# counter.net
KiCad netlist of a schematic drawn in EAGLE
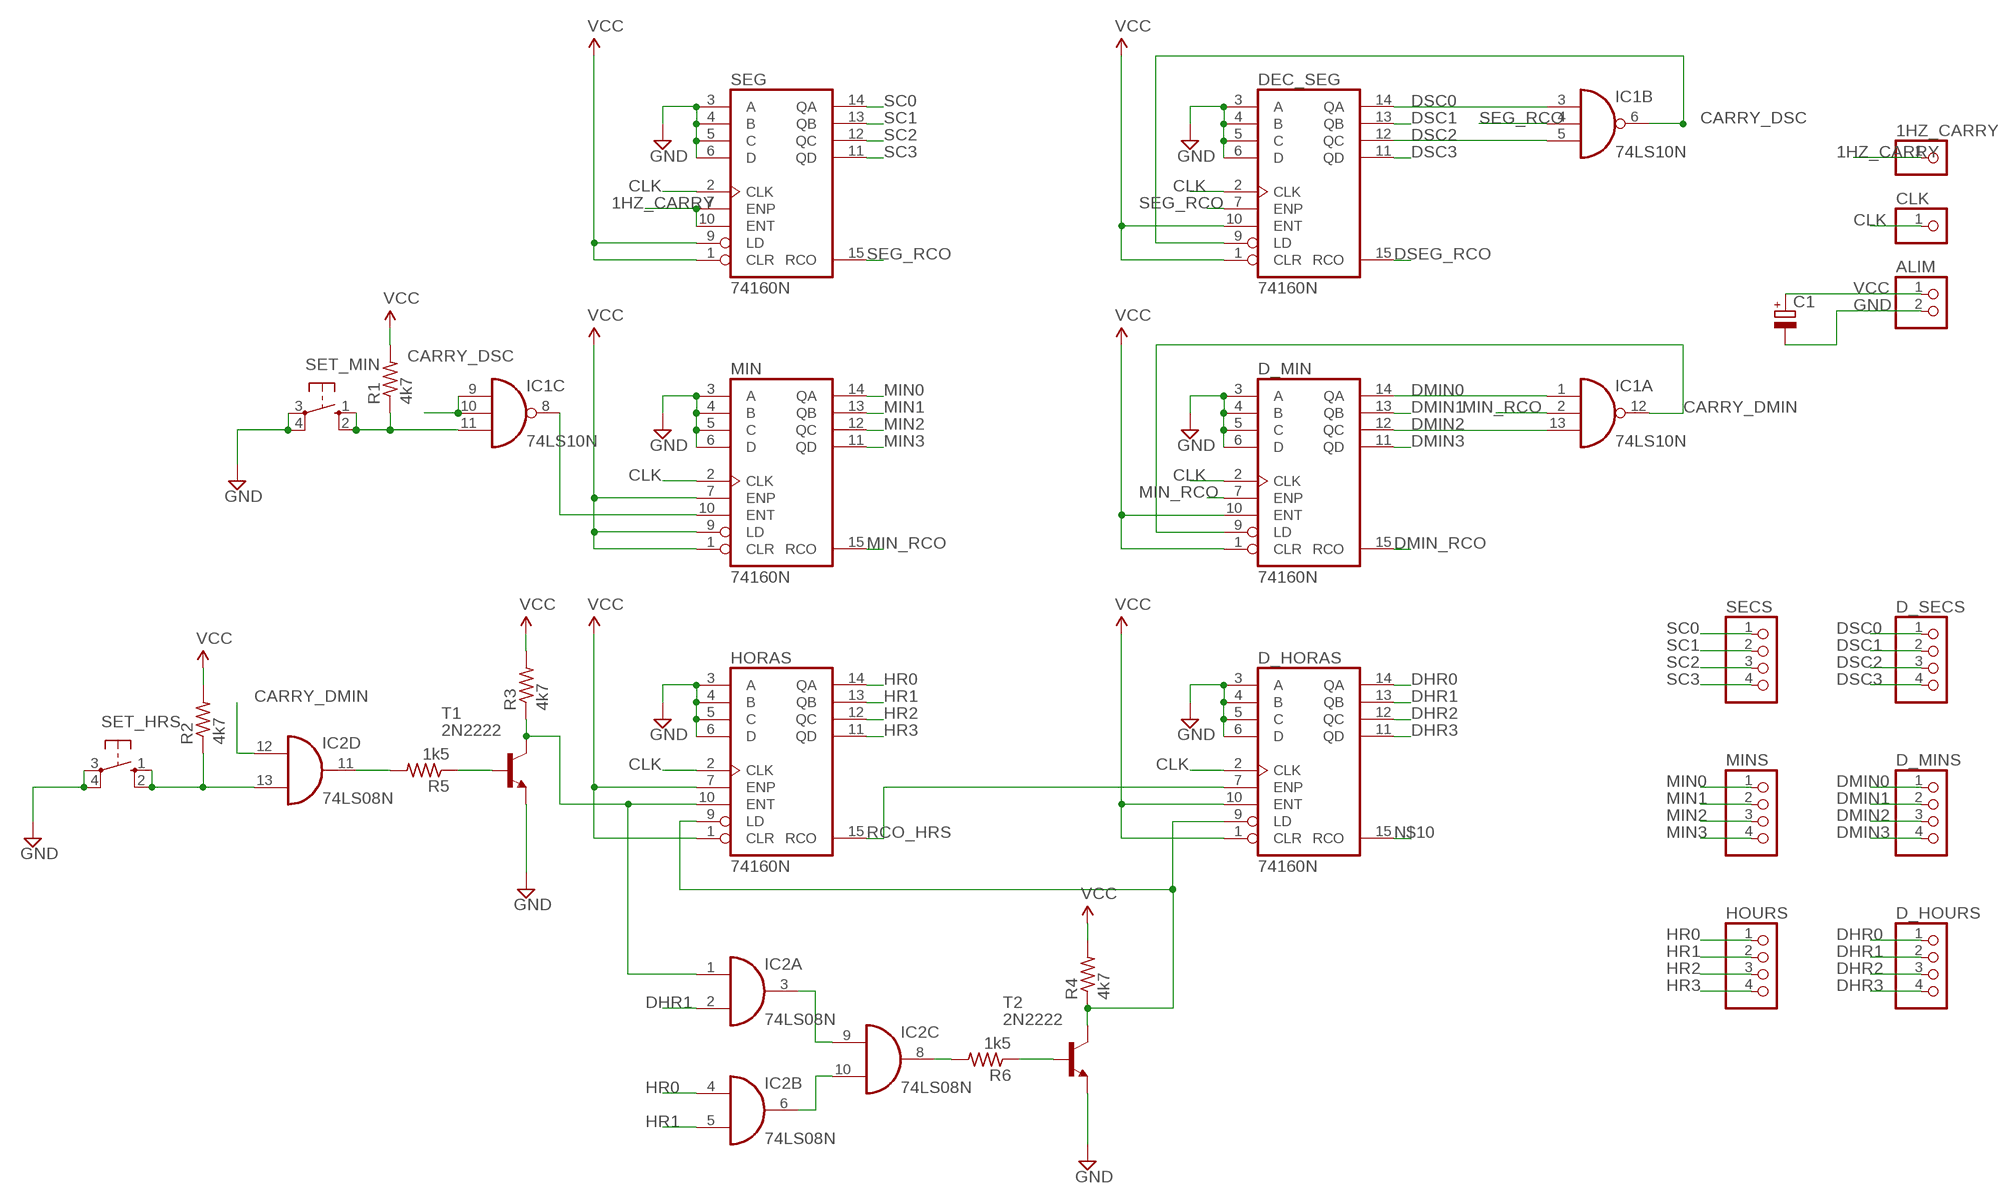
[diagram p0: schematic, sheet 1]

(export (version "E")
  (design (tool "Eeschema 10.0.6"))
  (components
    (comp (ref "1HZ_CARRY")
      (value "PINHD-1X1")
      (footprint "eagle-import:1X01")
      (libsource (lib "eagle-import") (part "PINHD-1X1"))
    )
    (comp (ref "ALIM")
      (value "PINHD-1X2")
      (footprint "eagle-import:1X02")
      (libsource (lib "eagle-import") (part "PINHD-1X2"))
    )
    (comp (ref "C1")
      (value "CPOL-EUE2-5")
      (footprint "eagle-import:E2-5")
      (libsource (lib "eagle-import") (part "CPOL-EUE2-5"))
    )
    (comp (ref "CLK")
      (value "PINHD-1X1")
      (footprint "eagle-import:1X01")
      (libsource (lib "eagle-import") (part "PINHD-1X1"))
    )
    (comp (ref "DEC_SEG")
      (value "74160N")
      (footprint "eagle-import:DIL16")
      (libsource (lib "eagle-import") (part "74160N"))
    )
    (comp (ref "D_HORAS")
      (value "74160N")
      (footprint "eagle-import:DIL16")
      (libsource (lib "eagle-import") (part "74160N"))
    )
    (comp (ref "D_HOURS")
      (value "PINHD-1X4")
      (footprint "eagle-import:1X04")
      (libsource (lib "eagle-import") (part "PINHD-1X4"))
    )
    (comp (ref "D_MIN")
      (value "74160N")
      (footprint "eagle-import:DIL16")
      (libsource (lib "eagle-import") (part "74160N"))
    )
    (comp (ref "D_MINS")
      (value "PINHD-1X4")
      (footprint "eagle-import:1X04")
      (libsource (lib "eagle-import") (part "PINHD-1X4"))
    )
    (comp (ref "D_SECS")
      (value "PINHD-1X4")
      (footprint "eagle-import:1X04")
      (libsource (lib "eagle-import") (part "PINHD-1X4"))
    )
    (comp (ref "HORAS")
      (value "74160N")
      (footprint "eagle-import:DIL16")
      (libsource (lib "eagle-import") (part "74160N"))
    )
    (comp (ref "HOURS")
      (value "PINHD-1X4")
      (footprint "eagle-import:1X04")
      (libsource (lib "eagle-import") (part "PINHD-1X4"))
    )
    (comp (ref "IC1")
      (value "74LS10N")
      (footprint "eagle-import:DIL14")
      (libsource (lib "eagle-import") (part "7410NLS"))
    )
    (comp (ref "IC2")
      (value "74LS08N")
      (footprint "eagle-import:DIL14")
      (libsource (lib "eagle-import") (part "7408NLS"))
    )
    (comp (ref "MIN")
      (value "74160N")
      (footprint "eagle-import:DIL16")
      (libsource (lib "eagle-import") (part "74160N"))
    )
    (comp (ref "MINS")
      (value "PINHD-1X4")
      (footprint "eagle-import:1X04")
      (libsource (lib "eagle-import") (part "PINHD-1X4"))
    )
    (comp (ref "R1")
      (value "4k7")
      (footprint "eagle-import:0204_7")
      (libsource (lib "eagle-import") (part "R-US_0204/7"))
    )
    (comp (ref "R2")
      (value "4k7")
      (footprint "eagle-import:0204_7")
      (libsource (lib "eagle-import") (part "R-US_0204/7"))
    )
    (comp (ref "R3")
      (value "4k7")
      (footprint "eagle-import:0204_7")
      (libsource (lib "eagle-import") (part "R-US_0204/7"))
    )
    (comp (ref "R4")
      (value "4k7")
      (footprint "eagle-import:0204_7")
      (libsource (lib "eagle-import") (part "R-US_0204/7"))
    )
    (comp (ref "R5")
      (value "1k5")
      (footprint "eagle-import:0204_7")
      (libsource (lib "eagle-import") (part "R-US_0204/7"))
    )
    (comp (ref "R6")
      (value "1k5")
      (footprint "eagle-import:0204_7")
      (libsource (lib "eagle-import") (part "R-US_0204/7"))
    )
    (comp (ref "SECS")
      (value "PINHD-1X4")
      (footprint "eagle-import:1X04")
      (libsource (lib "eagle-import") (part "PINHD-1X4"))
    )
    (comp (ref "SEG")
      (value "74160N")
      (footprint "eagle-import:DIL16")
      (libsource (lib "eagle-import") (part "74160N"))
    )
    (comp (ref "SET_HRS")
      (value "40-XX")
      (footprint "eagle-import:B3F-40XX")
      (fields (field (name "MF") "OMRON COMPONENTS USA") (field (name "MPN") "B3F-4000"))
      (libsource (lib "eagle-import") (part "40-XX"))
    )
    (comp (ref "SET_MIN")
      (value "40-XX")
      (footprint "eagle-import:B3F-40XX")
      (fields (field (name "MF") "OMRON COMPONENTS USA") (field (name "MPN") "B3F-4000"))
      (libsource (lib "eagle-import") (part "40-XX"))
    )
    (comp (ref "T1")
      (value "2N2222")
      (footprint "eagle-import:TO92-EBC-OVAL")
      (libsource (lib "eagle-import") (part "2N2222"))
    )
    (comp (ref "T2")
      (value "2N2222")
      (footprint "eagle-import:TO92-EBC-OVAL")
      (libsource (lib "eagle-import") (part "2N2222"))
    )
  )
  (nets
    (net (code "1") (name "/1HZ_CARRY") (class "Default")
      (node (ref "1HZ_CARRY") (pin "1") (pinfunction "1_1") (pintype "passive"))
      (node (ref "SEG") (pin "10") (pinfunction "ENT_10") (pintype "input"))
      (node (ref "SEG") (pin "7") (pinfunction "ENP_7") (pintype "input"))
    )
    (net (code "2") (name "/CARRY_DMIN") (class "Default")
      (node (ref "D_MIN") (pin "9") (pinfunction "LD_9") (pintype "input"))
      (node (ref "IC1") (pin "12") (pinfunction "O_12") (pintype "output"))
      (node (ref "IC2") (pin "12") (pinfunction "I0_12") (pintype "input"))
    )
    (net (code "3") (name "/CARRY_DSC") (class "Default")
      (node (ref "DEC_SEG") (pin "9") (pinfunction "LD_9") (pintype "input"))
      (node (ref "IC1") (pin "10") (pinfunction "I1_10") (pintype "input"))
      (node (ref "IC1") (pin "6") (pinfunction "O_6") (pintype "output"))
      (node (ref "IC1") (pin "9") (pinfunction "I0_9") (pintype "input"))
    )
    (net (code "4") (name "/CLK") (class "Default")
      (node (ref "CLK") (pin "1") (pinfunction "1_1") (pintype "passive"))
      (node (ref "DEC_SEG") (pin "2") (pinfunction "CLK_2") (pintype "input"))
      (node (ref "D_HORAS") (pin "2") (pinfunction "CLK_2") (pintype "input"))
      (node (ref "D_MIN") (pin "2") (pinfunction "CLK_2") (pintype "input"))
      (node (ref "HORAS") (pin "2") (pinfunction "CLK_2") (pintype "input"))
      (node (ref "MIN") (pin "2") (pinfunction "CLK_2") (pintype "input"))
      (node (ref "SEG") (pin "2") (pinfunction "CLK_2") (pintype "input"))
    )
    (net (code "5") (name "/DHR0") (class "Default")
      (node (ref "D_HORAS") (pin "14") (pinfunction "QA_14") (pintype "output"))
      (node (ref "D_HOURS") (pin "1") (pinfunction "1_1") (pintype "passive"))
    )
    (net (code "6") (name "/DHR1") (class "Default")
      (node (ref "D_HORAS") (pin "13") (pinfunction "QB_13") (pintype "output"))
      (node (ref "D_HOURS") (pin "2") (pinfunction "2_2") (pintype "passive"))
      (node (ref "IC2") (pin "2") (pinfunction "I1_2") (pintype "input"))
    )
    (net (code "7") (name "/DHR2") (class "Default")
      (node (ref "D_HORAS") (pin "12") (pinfunction "QC_12") (pintype "output"))
      (node (ref "D_HOURS") (pin "3") (pinfunction "3_3") (pintype "passive"))
    )
    (net (code "8") (name "/DHR3") (class "Default")
      (node (ref "D_HORAS") (pin "11") (pinfunction "QD_11") (pintype "output"))
      (node (ref "D_HOURS") (pin "4") (pinfunction "4_4") (pintype "passive"))
    )
    (net (code "9") (name "/DMIN0") (class "Default")
      (node (ref "D_MIN") (pin "14") (pinfunction "QA_14") (pintype "output"))
      (node (ref "D_MINS") (pin "1") (pinfunction "1_1") (pintype "passive"))
      (node (ref "IC1") (pin "1") (pinfunction "I0_1") (pintype "input"))
    )
    (net (code "10") (name "/DMIN1") (class "Default")
      (node (ref "D_MIN") (pin "13") (pinfunction "QB_13") (pintype "output"))
      (node (ref "D_MINS") (pin "2") (pinfunction "2_2") (pintype "passive"))
    )
    (net (code "11") (name "/DMIN2") (class "Default")
      (node (ref "D_MIN") (pin "12") (pinfunction "QC_12") (pintype "output"))
      (node (ref "D_MINS") (pin "3") (pinfunction "3_3") (pintype "passive"))
      (node (ref "IC1") (pin "13") (pinfunction "I2_13") (pintype "input"))
    )
    (net (code "12") (name "/DMIN3") (class "Default")
      (node (ref "D_MIN") (pin "11") (pinfunction "QD_11") (pintype "output"))
      (node (ref "D_MINS") (pin "4") (pinfunction "4_4") (pintype "passive"))
    )
    (net (code "13") (name "/DMIN_RCO") (class "Default")
      (node (ref "D_MIN") (pin "15") (pinfunction "RCO_15") (pintype "output"))
    )
    (net (code "14") (name "/DSC0") (class "Default")
      (node (ref "DEC_SEG") (pin "14") (pinfunction "QA_14") (pintype "output"))
      (node (ref "D_SECS") (pin "1") (pinfunction "1_1") (pintype "passive"))
      (node (ref "IC1") (pin "3") (pinfunction "I0_3") (pintype "input"))
    )
    (net (code "15") (name "/DSC1") (class "Default")
      (node (ref "DEC_SEG") (pin "13") (pinfunction "QB_13") (pintype "output"))
      (node (ref "D_SECS") (pin "2") (pinfunction "2_2") (pintype "passive"))
    )
    (net (code "16") (name "/DSC2") (class "Default")
      (node (ref "DEC_SEG") (pin "12") (pinfunction "QC_12") (pintype "output"))
      (node (ref "D_SECS") (pin "3") (pinfunction "3_3") (pintype "passive"))
      (node (ref "IC1") (pin "5") (pinfunction "I2_5") (pintype "input"))
    )
    (net (code "17") (name "/DSC3") (class "Default")
      (node (ref "DEC_SEG") (pin "11") (pinfunction "QD_11") (pintype "output"))
      (node (ref "D_SECS") (pin "4") (pinfunction "4_4") (pintype "passive"))
    )
    (net (code "18") (name "/DSEG_RCO") (class "Default")
      (node (ref "DEC_SEG") (pin "15") (pinfunction "RCO_15") (pintype "output"))
    )
    (net (code "19") (name "/HR0") (class "Default")
      (node (ref "HORAS") (pin "14") (pinfunction "QA_14") (pintype "output"))
      (node (ref "HOURS") (pin "1") (pinfunction "1_1") (pintype "passive"))
      (node (ref "IC2") (pin "4") (pinfunction "I0_4") (pintype "input"))
    )
    (net (code "20") (name "/HR1") (class "Default")
      (node (ref "HORAS") (pin "13") (pinfunction "QB_13") (pintype "output"))
      (node (ref "HOURS") (pin "2") (pinfunction "2_2") (pintype "passive"))
      (node (ref "IC2") (pin "5") (pinfunction "I1_5") (pintype "input"))
    )
    (net (code "21") (name "/HR2") (class "Default")
      (node (ref "HORAS") (pin "12") (pinfunction "QC_12") (pintype "output"))
      (node (ref "HOURS") (pin "3") (pinfunction "3_3") (pintype "passive"))
    )
    (net (code "22") (name "/HR3") (class "Default")
      (node (ref "HORAS") (pin "11") (pinfunction "QD_11") (pintype "output"))
      (node (ref "HOURS") (pin "4") (pinfunction "4_4") (pintype "passive"))
    )
    (net (code "23") (name "/MIN0") (class "Default")
      (node (ref "MIN") (pin "14") (pinfunction "QA_14") (pintype "output"))
      (node (ref "MINS") (pin "1") (pinfunction "1_1") (pintype "passive"))
    )
    (net (code "24") (name "/MIN1") (class "Default")
      (node (ref "MIN") (pin "13") (pinfunction "QB_13") (pintype "output"))
      (node (ref "MINS") (pin "2") (pinfunction "2_2") (pintype "passive"))
    )
    (net (code "25") (name "/MIN2") (class "Default")
      (node (ref "MIN") (pin "12") (pinfunction "QC_12") (pintype "output"))
      (node (ref "MINS") (pin "3") (pinfunction "3_3") (pintype "passive"))
    )
    (net (code "26") (name "/MIN3") (class "Default")
      (node (ref "MIN") (pin "11") (pinfunction "QD_11") (pintype "output"))
      (node (ref "MINS") (pin "4") (pinfunction "4_4") (pintype "passive"))
    )
    (net (code "27") (name "/MIN_RCO") (class "Default")
      (node (ref "D_MIN") (pin "7") (pinfunction "ENP_7") (pintype "input"))
      (node (ref "IC1") (pin "2") (pinfunction "I1_2") (pintype "input"))
      (node (ref "MIN") (pin "15") (pinfunction "RCO_15") (pintype "output"))
    )
    (net (code "28") (name "/N$10") (class "Default")
      (node (ref "D_HORAS") (pin "15") (pinfunction "RCO_15") (pintype "output"))
    )
    (net (code "29") (name "/RCO_HRS") (class "Default")
      (node (ref "D_HORAS") (pin "7") (pinfunction "ENP_7") (pintype "input"))
      (node (ref "HORAS") (pin "15") (pinfunction "RCO_15") (pintype "output"))
    )
    (net (code "30") (name "/SC0") (class "Default")
      (node (ref "SECS") (pin "1") (pinfunction "1_1") (pintype "passive"))
      (node (ref "SEG") (pin "14") (pinfunction "QA_14") (pintype "output"))
    )
    (net (code "31") (name "/SC1") (class "Default")
      (node (ref "SECS") (pin "2") (pinfunction "2_2") (pintype "passive"))
      (node (ref "SEG") (pin "13") (pinfunction "QB_13") (pintype "output"))
    )
    (net (code "32") (name "/SC2") (class "Default")
      (node (ref "SECS") (pin "3") (pinfunction "3_3") (pintype "passive"))
      (node (ref "SEG") (pin "12") (pinfunction "QC_12") (pintype "output"))
    )
    (net (code "33") (name "/SC3") (class "Default")
      (node (ref "SECS") (pin "4") (pinfunction "4_4") (pintype "passive"))
      (node (ref "SEG") (pin "11") (pinfunction "QD_11") (pintype "output"))
    )
    (net (code "34") (name "/SEG_RCO") (class "Default")
      (node (ref "DEC_SEG") (pin "7") (pinfunction "ENP_7") (pintype "input"))
      (node (ref "IC1") (pin "4") (pinfunction "I1_4") (pintype "input"))
      (node (ref "SEG") (pin "15") (pinfunction "RCO_15") (pintype "output"))
    )
    (net (code "35") (name "GND") (class "Default")
      (node (ref "ALIM") (pin "2") (pinfunction "2_2") (pintype "passive"))
      (node (ref "C1") (pin "-") (pinfunction "-_-") (pintype "passive"))
      (node (ref "DEC_SEG") (pin "3") (pinfunction "A_3") (pintype "input"))
      (node (ref "DEC_SEG") (pin "4") (pinfunction "B_4") (pintype "input"))
      (node (ref "DEC_SEG") (pin "5") (pinfunction "C_5") (pintype "input"))
      (node (ref "DEC_SEG") (pin "6") (pinfunction "D_6") (pintype "input"))
      (node (ref "D_HORAS") (pin "3") (pinfunction "A_3") (pintype "input"))
      (node (ref "D_HORAS") (pin "4") (pinfunction "B_4") (pintype "input"))
      (node (ref "D_HORAS") (pin "5") (pinfunction "C_5") (pintype "input"))
      (node (ref "D_HORAS") (pin "6") (pinfunction "D_6") (pintype "input"))
      (node (ref "D_MIN") (pin "3") (pinfunction "A_3") (pintype "input"))
      (node (ref "D_MIN") (pin "4") (pinfunction "B_4") (pintype "input"))
      (node (ref "D_MIN") (pin "5") (pinfunction "C_5") (pintype "input"))
      (node (ref "D_MIN") (pin "6") (pinfunction "D_6") (pintype "input"))
      (node (ref "HORAS") (pin "3") (pinfunction "A_3") (pintype "input"))
      (node (ref "HORAS") (pin "4") (pinfunction "B_4") (pintype "input"))
      (node (ref "HORAS") (pin "5") (pinfunction "C_5") (pintype "input"))
      (node (ref "HORAS") (pin "6") (pinfunction "D_6") (pintype "input"))
      (node (ref "MIN") (pin "3") (pinfunction "A_3") (pintype "input"))
      (node (ref "MIN") (pin "4") (pinfunction "B_4") (pintype "input"))
      (node (ref "MIN") (pin "5") (pinfunction "C_5") (pintype "input"))
      (node (ref "MIN") (pin "6") (pinfunction "D_6") (pintype "input"))
      (node (ref "SEG") (pin "3") (pinfunction "A_3") (pintype "input"))
      (node (ref "SEG") (pin "4") (pinfunction "B_4") (pintype "input"))
      (node (ref "SEG") (pin "5") (pinfunction "C_5") (pintype "input"))
      (node (ref "SEG") (pin "6") (pinfunction "D_6") (pintype "input"))
      (node (ref "SET_HRS") (pin "3") (pinfunction "P_3") (pintype "passive"))
      (node (ref "SET_HRS") (pin "4") (pinfunction "P1_4") (pintype "passive"))
      (node (ref "SET_MIN") (pin "3") (pinfunction "P_3") (pintype "passive"))
      (node (ref "SET_MIN") (pin "4") (pinfunction "P1_4") (pintype "passive"))
      (node (ref "T1") (pin "E") (pinfunction "E_E") (pintype "passive"))
      (node (ref "T2") (pin "E") (pinfunction "E_E") (pintype "passive"))
    )
    (net (code "36") (name "Net-(D_HORASA-LD)") (class "Default")
      (node (ref "D_HORAS") (pin "9") (pinfunction "LD_9") (pintype "input"))
      (node (ref "HORAS") (pin "9") (pinfunction "LD_9") (pintype "input"))
      (node (ref "R4") (pin "1") (pinfunction "1_1") (pintype "passive"))
      (node (ref "T2") (pin "C") (pinfunction "C_C") (pintype "passive"))
    )
    (net (code "37") (name "Net-(HORASA-ENT)") (class "Default")
      (node (ref "HORAS") (pin "10") (pinfunction "ENT_10") (pintype "input"))
      (node (ref "IC2") (pin "1") (pinfunction "I0_1") (pintype "input"))
      (node (ref "R3") (pin "1") (pinfunction "1_1") (pintype "passive"))
      (node (ref "T1") (pin "C") (pinfunction "C_C") (pintype "passive"))
    )
    (net (code "38") (name "Net-(IC1C-I2)") (class "Default")
      (node (ref "IC1") (pin "11") (pinfunction "I2_11") (pintype "input"))
      (node (ref "R1") (pin "1") (pinfunction "1_1") (pintype "passive"))
      (node (ref "SET_MIN") (pin "1") (pinfunction "S_1") (pintype "passive"))
      (node (ref "SET_MIN") (pin "2") (pinfunction "S1_2") (pintype "passive"))
    )
    (net (code "39") (name "Net-(IC1C-O)") (class "Default")
      (node (ref "IC1") (pin "8") (pinfunction "O_8") (pintype "output"))
      (node (ref "MIN") (pin "10") (pinfunction "ENT_10") (pintype "input"))
    )
    (net (code "40") (name "Net-(IC2A-O)") (class "Default")
      (node (ref "IC2") (pin "3") (pinfunction "O_3") (pintype "output"))
      (node (ref "IC2") (pin "9") (pinfunction "I0_9") (pintype "input"))
    )
    (net (code "41") (name "Net-(IC2B-O)") (class "Default")
      (node (ref "IC2") (pin "10") (pinfunction "I1_10") (pintype "input"))
      (node (ref "IC2") (pin "6") (pinfunction "O_6") (pintype "output"))
    )
    (net (code "42") (name "Net-(IC2C-O)") (class "Default")
      (node (ref "IC2") (pin "8") (pinfunction "O_8") (pintype "output"))
      (node (ref "R6") (pin "2") (pinfunction "2_2") (pintype "passive"))
    )
    (net (code "43") (name "Net-(IC2D-I1)") (class "Default")
      (node (ref "IC2") (pin "13") (pinfunction "I1_13") (pintype "input"))
      (node (ref "R2") (pin "1") (pinfunction "1_1") (pintype "passive"))
      (node (ref "SET_HRS") (pin "1") (pinfunction "S_1") (pintype "passive"))
      (node (ref "SET_HRS") (pin "2") (pinfunction "S1_2") (pintype "passive"))
    )
    (net (code "44") (name "Net-(IC2D-O)") (class "Default")
      (node (ref "IC2") (pin "11") (pinfunction "O_11") (pintype "output"))
      (node (ref "R5") (pin "2") (pinfunction "2_2") (pintype "passive"))
    )
    (net (code "45") (name "Net-(R5-Pad1)") (class "Default")
      (node (ref "R5") (pin "1") (pinfunction "1_1") (pintype "passive"))
      (node (ref "T1") (pin "B") (pinfunction "B_B") (pintype "passive"))
    )
    (net (code "46") (name "Net-(R6-Pad1)") (class "Default")
      (node (ref "R6") (pin "1") (pinfunction "1_1") (pintype "passive"))
      (node (ref "T2") (pin "B") (pinfunction "B_B") (pintype "passive"))
    )
    (net (code "47") (name "VCC") (class "Default")
      (node (ref "ALIM") (pin "1") (pinfunction "1_1") (pintype "passive"))
      (node (ref "C1") (pin "+") (pinfunction "+_+") (pintype "passive"))
      (node (ref "DEC_SEG") (pin "1") (pinfunction "CLR_1") (pintype "input"))
      (node (ref "DEC_SEG") (pin "10") (pinfunction "ENT_10") (pintype "input"))
      (node (ref "D_HORAS") (pin "1") (pinfunction "CLR_1") (pintype "input"))
      (node (ref "D_HORAS") (pin "10") (pinfunction "ENT_10") (pintype "input"))
      (node (ref "D_MIN") (pin "1") (pinfunction "CLR_1") (pintype "input"))
      (node (ref "D_MIN") (pin "10") (pinfunction "ENT_10") (pintype "input"))
      (node (ref "HORAS") (pin "1") (pinfunction "CLR_1") (pintype "input"))
      (node (ref "HORAS") (pin "7") (pinfunction "ENP_7") (pintype "input"))
      (node (ref "MIN") (pin "1") (pinfunction "CLR_1") (pintype "input"))
      (node (ref "MIN") (pin "7") (pinfunction "ENP_7") (pintype "input"))
      (node (ref "MIN") (pin "9") (pinfunction "LD_9") (pintype "input"))
      (node (ref "R1") (pin "2") (pinfunction "2_2") (pintype "passive"))
      (node (ref "R2") (pin "2") (pinfunction "2_2") (pintype "passive"))
      (node (ref "R3") (pin "2") (pinfunction "2_2") (pintype "passive"))
      (node (ref "R4") (pin "2") (pinfunction "2_2") (pintype "passive"))
      (node (ref "SEG") (pin "1") (pinfunction "CLR_1") (pintype "input"))
      (node (ref "SEG") (pin "9") (pinfunction "LD_9") (pintype "input"))
    )
  )
)
